# Hydro_Node_Schematic.net
KiCad netlist of a schematic drawn in Altium Designer
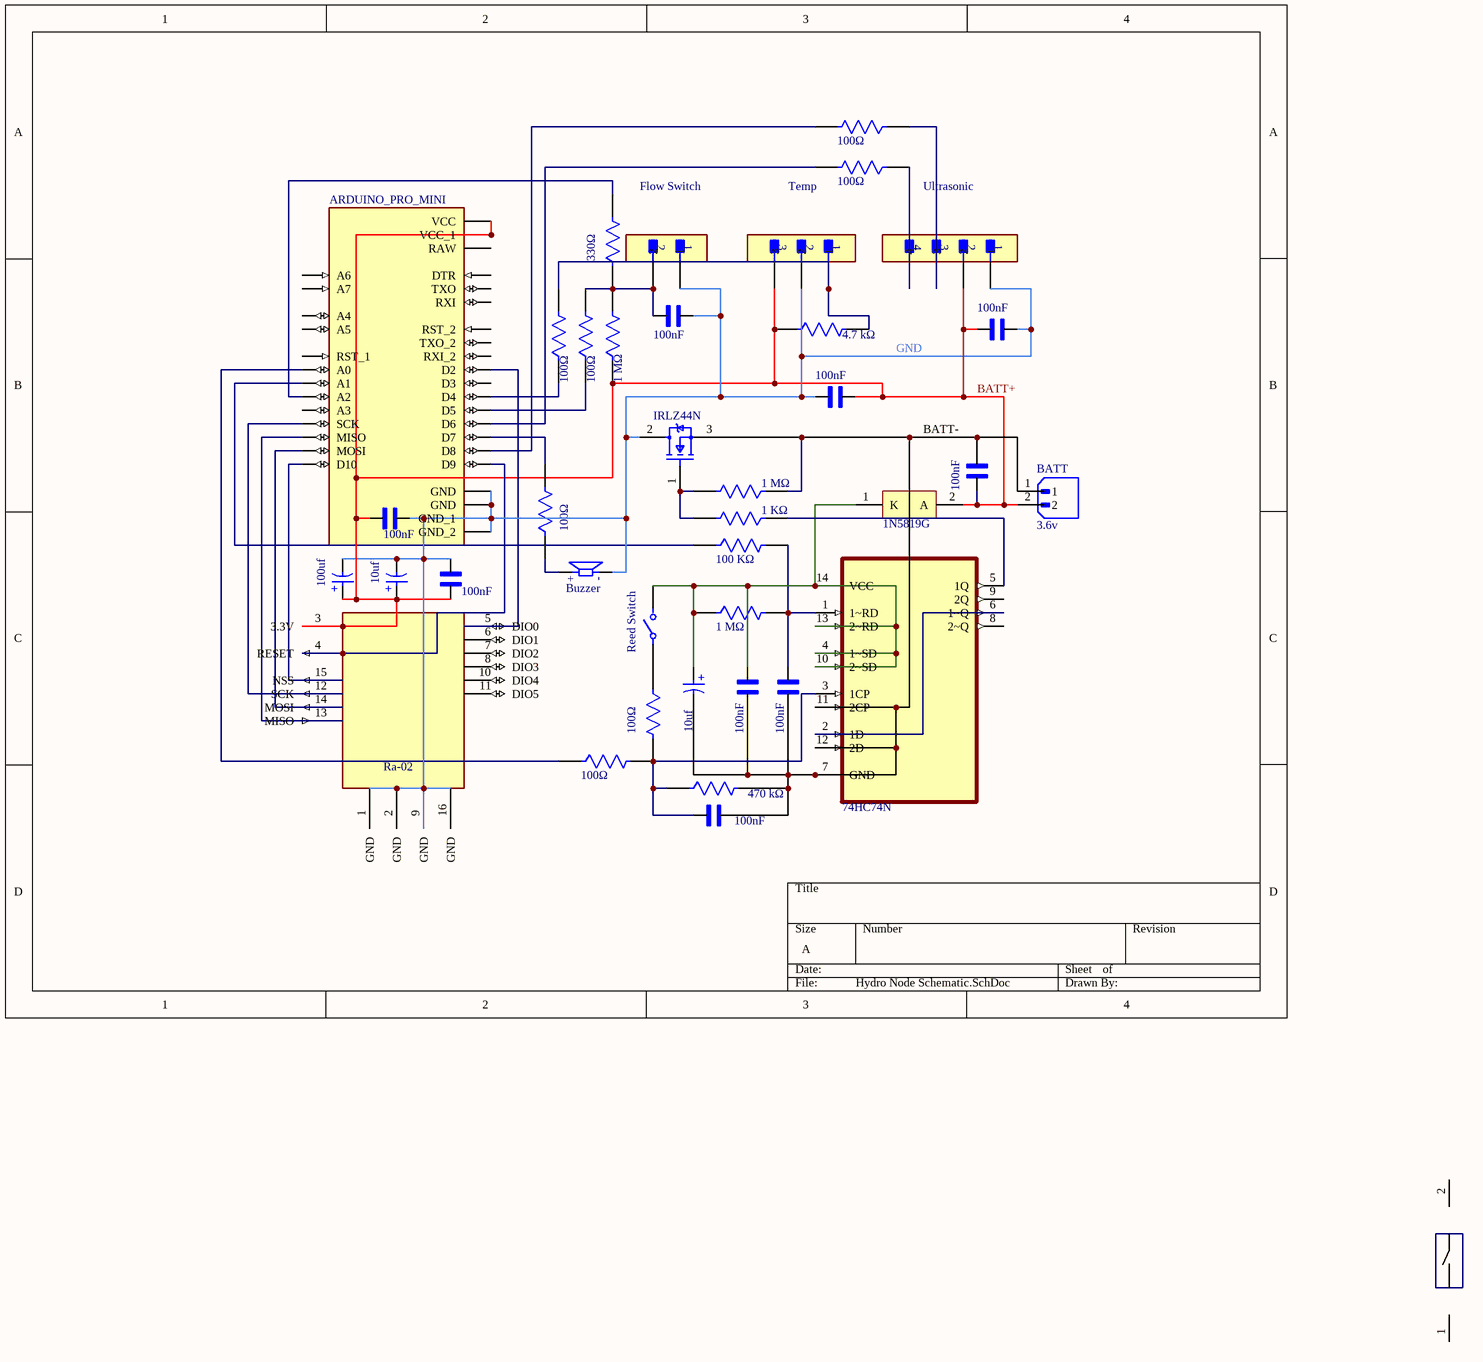
[diagram p0: Hydro Node Schematic.SchDoc]

(export (version "E")
  (design (tool "Eeschema 10.0.6"))
  (components
    (comp (ref "BATT")
      (value "3.6v")
      (footprint "JST_B2B-XH-A_(LF)(SN)")
      (description "Connector Header Through Hole 2 position 0.098 (2.50mm)")
      (fields (field (name "MF") "JST Sales") (field (name "MP") "B2B-XH-A (LF)(SN)"))
      (libsource (lib "B2B-XH-A__LF__SN_") (part "B2B-XH-A_(LF)(SN)"))
    )
    (comp (ref "C1")
      (value "100nF")
      (footprint "CAPRR508W50L508T317H508")
      (description "SR Series 5.08x5.08 mm 100 nF 50 V Â±20% Tol. Z5U Radial Lead/SkyCapÂ®")
      (fields (field (name "MF") "AVX") (field (name "MP") "SR215E104MARTR1"))
      (libsource (lib "SR215E104MARTR1.") (part "SR215E104MARTR1."))
    )
    (comp (ref "C2")
      (value "100nF")
      (footprint "CAPRR508W50L508T317H508")
      (description "SR Series 5.08x5.08 mm 100 nF 50 V Â±20% Tol. Z5U Radial Lead/SkyCapÂ®")
      (fields (field (name "MF") "AVX") (field (name "MP") "SR215E104MARTR1"))
      (libsource (lib "SR215E104MARTR1.") (part "SR215E104MARTR1."))
    )
    (comp (ref "C3")
      (value "100nF")
      (footprint "CAPRR508W50L508T317H508")
      (description "SR Series 5.08x5.08 mm 100 nF 50 V Â±20% Tol. Z5U Radial Lead/SkyCapÂ®")
      (fields (field (name "MF") "AVX") (field (name "MP") "SR215E104MARTR1"))
      (libsource (lib "SR215E104MARTR1.") (part "SR215E104MARTR1."))
    )
    (comp (ref "C4")
      (value "100nF")
      (footprint "CAPRR508W50L508T317H508")
      (description "SR Series 5.08x5.08 mm 100 nF 50 V Â±20% Tol. Z5U Radial Lead/SkyCapÂ®")
      (fields (field (name "MF") "AVX") (field (name "MP") "SR215E104MARTR1"))
      (libsource (lib "") (part "SR215E104MARTR1._1"))
    )
    (comp (ref "C5")
      (value "100nF")
      (footprint "CAPRR508W50L508T317H508")
      (description "SR Series 5.08x5.08 mm 100 nF 50 V Â±20% Tol. Z5U Radial Lead/SkyCapÂ®")
      (fields (field (name "MF") "AVX") (field (name "MP") "SR215E104MARTR1"))
      (libsource (lib "") (part "SR215E104MARTR1._2"))
    )
    (comp (ref "C6")
      (value "100nF")
      (footprint "CAPRR508W50L508T317H508")
      (description "SR Series 5.08x5.08 mm 100 nF 50 V Â±20% Tol. Z5U Radial Lead/SkyCapÂ®")
      (fields (field (name "MF") "AVX") (field (name "MP") "SR215E104MARTR1"))
      (libsource (lib "") (part "SR215E104MARTR1._3"))
    )
    (comp (ref "C7")
      (value "100uf")
      (footprint "WCAP-ATLL_D5H11")
      (description "WCAP-ATLL Aluminum Electrolytic Capacitors")
      (fields (field (name "TOLERANCE") "20%"))
      (libsource (lib "Altium Content Vault") (part "Capacitor_Polarized"))
    )
    (comp (ref "C8")
      (value "10uf")
      (footprint "WCAP-ATLL_D5H11")
      (description "Alum. Electrolytic Cap 10UF 50V 5MM Radial Wcap-atll, Lifetime 4000H +105OC")
      (fields (field (name "TOLERANCE") "20%"))
      (libsource (lib "Altium Content Vault") (part "Capacitor_Polarized"))
    )
    (comp (ref "C9")
      (value "10uf")
      (footprint "WCAP-ATLL_D5H11")
      (description "Alum. Electrolytic Cap 10UF 50V 5MM Radial Wcap-atll, Lifetime 4000H +105OC")
      (fields (field (name "TOLERANCE") "20%"))
      (libsource (lib "Altium Content Vault") (part "Capacitor_Polarized"))
    )
    (comp (ref "C10")
      (value "100nF")
      (footprint "CAPRR508W50L508T317H508")
      (description "SR Series 5.08x5.08 mm 100 nF 50 V Â±20% Tol. Z5U Radial Lead/SkyCapÂ®")
      (fields (field (name "MF") "AVX") (field (name "MP") "SR215E104MARTR1"))
      (libsource (lib "") (part "SR215E104MARTR1._1"))
    )
    (comp (ref "C11")
      (value "100nF")
      (footprint "CAPRR508W50L508T317H508")
      (description "SR Series 5.08x5.08 mm 100 nF 50 V Â±20% Tol. Z5U Radial Lead/SkyCapÂ®")
      (fields (field (name "MF") "AVX") (field (name "MP") "SR215E104MARTR1"))
      (libsource (lib "") (part "SR215E104MARTR1._1"))
    )
    (comp (ref "C12")
      (value "100nF")
      (footprint "CAPRR508W50L508T317H508")
      (description "SR Series 5.08x5.08 mm 100 nF 50 V Â±20% Tol. Z5U Radial Lead/SkyCapÂ®")
      (fields (field (name "MF") "AVX") (field (name "MP") "SR215E104MARTR1"))
      (libsource (lib "SR215E104MARTR1.") (part "SR215E104MARTR1."))
    )
    (comp (ref "D1")
      (value "1N5819G")
      (footprint "ONSC-AXIAL_LEAD-2-59-10_P")
      (description "Rectifier, 2-Pin Axial_Lead, Pb-Free, Bulk Bag")
      (fields (field (name "MANUFACTURER") "On Semiconductor"))
      (libsource (lib "Altium Content Vault") (part "ONSC-D-K1A2-2_A"))
    )
    (comp (ref "J1")
      (value "Flow Switch")
      (footprint "FP-B2B-XH-AM_LF_SN-MFG")
      (description "CONN HEADER VERT 2POS 2.5MM")
      (libsource (lib "Altium Content Vault") (part "3bc925449376181038e59eaffc5286c"))
    )
    (comp (ref "J2")
      (value "Temp")
      (footprint "FP-B3B-XH-A_LF_SN-MFG")
      (description "CONN HEADER VERT 3POS 2.5MM")
      (libsource (lib "Altium Content Vault") (part "0d3f023dd272f625e17a2be33dea85f"))
    )
    (comp (ref "J3")
      (value "Ultrasonic")
      (footprint "FP-B4B-XH-A_LF_SN-MFG")
      (description "CONN HEADER VERT 4POS 2.5MM")
      (libsource (lib "Altium Content Vault") (part "299a8cea1bdcbc3624fe62c390fa72c"))
    )
    (comp (ref "LS1")
      (value "Buzzer")
      (footprint "CUI_CPT-1255C-090:CUI_CPT-1255C-090")
      (description "12 mm, 20 Vp-p, 80 dB, Through Hole, Piezo Audio Transducer Buzzer")
      (fields (field (name "MF") "Same Sky") (field (name "MP") "CPT-1255C-090"))
      (libsource (lib "CPT-1255C-090") (part "CPT-1255C-090"))
    )
    (comp (ref "Q1")
      (value "IRLZ44N")
      (footprint "FP-PG-TO220-3-MFG")
      (description "MOSFET N-CH 55V 47A TO220AB")
      (libsource (lib "Altium Content Vault") (part "b09f7f152735e370c1ea22a33fa83d6"))
    )
    (comp (ref "R1")
      (value "100Ω")
      (footprint "FP-MFR-25-MFG")
      (description "RES 1.18K OHM 1/4W 1% AXIAL")
      (fields (field (name "MANUFACTURER") "Yageo") (field (name "TOLERANCE") "1%"))
      (libsource (lib "Altium Content Vault") (part "1029c3af85768c4190bb7ad29bc67b5"))
    )
    (comp (ref "R2")
      (value "100Ω")
      (footprint "FP-MFR-25-MFG")
      (description "RES 1.18K OHM 1/4W 1% AXIAL")
      (fields (field (name "MANUFACTURER") "Yageo") (field (name "TOLERANCE") "1%"))
      (libsource (lib "Altium Content Vault") (part "1029c3af85768c4190bb7ad29bc67b5"))
    )
    (comp (ref "R3")
      (value "330Ω")
      (footprint "FP-MFR-25-MFG")
      (description "RES 1.18K OHM 1/4W 1% AXIAL")
      (fields (field (name "MANUFACTURER") "Yageo") (field (name "TOLERANCE") "1%"))
      (libsource (lib "Altium Content Vault") (part "1029c3af85768c4190bb7ad29bc67b5"))
    )
    (comp (ref "R4")
      (value "100Ω")
      (footprint "FP-MFR-25-MFG")
      (description "RES 1.18K OHM 1/4W 1% AXIAL")
      (fields (field (name "MANUFACTURER") "Yageo") (field (name "TOLERANCE") "1%"))
      (libsource (lib "Altium Content Vault") (part "1029c3af85768c4190bb7ad29bc67b5"))
    )
    (comp (ref "R5")
      (value "100Ω")
      (footprint "FP-MFR-25-MFG")
      (description "RES 1.18K OHM 1/4W 1% AXIAL")
      (fields (field (name "MANUFACTURER") "Yageo") (field (name "TOLERANCE") "1%"))
      (libsource (lib "Altium Content Vault") (part "1029c3af85768c4190bb7ad29bc67b5"))
    )
    (comp (ref "R6")
      (value "1 MΩ")
      (footprint "FP-MFR-25-MFG")
      (description "RES 1.18K OHM 1/4W 1% AXIAL")
      (fields (field (name "MANUFACTURER") "Yageo") (field (name "TOLERANCE") "1%"))
      (libsource (lib "Altium Content Vault") (part "1029c3af85768c4190bb7ad29bc67b5"))
    )
    (comp (ref "R7")
      (value "4.7 kΩ")
      (footprint "FP-MFR-25-MFG")
      (description "RES 1.18K OHM 1/4W 1% AXIAL")
      (fields (field (name "MANUFACTURER") "Yageo") (field (name "TOLERANCE") "1%"))
      (libsource (lib "Altium Content Vault") (part "1029c3af85768c4190bb7ad29bc67b5"))
    )
    (comp (ref "R8")
      (value "1 MΩ")
      (footprint "FP-MFR-25-MFG")
      (description "RES 1.18K OHM 1/4W 1% AXIAL")
      (fields (field (name "MANUFACTURER") "Yageo") (field (name "TOLERANCE") "1%"))
      (libsource (lib "Altium Content Vault") (part "1029c3af85768c4190bb7ad29bc67b5"))
    )
    (comp (ref "R9")
      (value "100 KΩ")
      (footprint "FP-MFR-25-MFG")
      (description "RES 1.18K OHM 1/4W 1% AXIAL")
      (fields (field (name "MANUFACTURER") "Yageo") (field (name "TOLERANCE") "1%"))
      (libsource (lib "Altium Content Vault") (part "1029c3af85768c4190bb7ad29bc67b5"))
    )
    (comp (ref "R10")
      (value "1 KΩ")
      (footprint "FP-MFR-25-MFG")
      (description "RES 1.18K OHM 1/4W 1% AXIAL")
      (fields (field (name "MANUFACTURER") "Yageo") (field (name "TOLERANCE") "1%"))
      (libsource (lib "Altium Content Vault") (part "1029c3af85768c4190bb7ad29bc67b5"))
    )
    (comp (ref "R11")
      (value "1 MΩ")
      (footprint "FP-MFR-25-MFG")
      (description "RES 1.18K OHM 1/4W 1% AXIAL")
      (fields (field (name "MANUFACTURER") "Yageo") (field (name "TOLERANCE") "1%"))
      (libsource (lib "Altium Content Vault") (part "1029c3af85768c4190bb7ad29bc67b5"))
    )
    (comp (ref "R12")
      (value "100Ω")
      (footprint "FP-MFR-25-MFG")
      (description "RES 1.18K OHM 1/4W 1% AXIAL")
      (fields (field (name "MANUFACTURER") "Yageo") (field (name "TOLERANCE") "1%"))
      (libsource (lib "Altium Content Vault") (part "1029c3af85768c4190bb7ad29bc67b5"))
    )
    (comp (ref "R13")
      (value "100Ω")
      (footprint "FP-MFR-25-MFG")
      (description "RES 1.18K OHM 1/4W 1% AXIAL")
      (fields (field (name "MANUFACTURER") "Yageo") (field (name "TOLERANCE") "1%"))
      (libsource (lib "Altium Content Vault") (part "1029c3af85768c4190bb7ad29bc67b5"))
    )
    (comp (ref "R14")
      (value "470 kΩ")
      (footprint "FP-MFR-25-MFG")
      (description "RES 1.18K OHM 1/4W 1% AXIAL")
      (fields (field (name "MANUFACTURER") "Yageo") (field (name "TOLERANCE") "1%"))
      (libsource (lib "Altium Content Vault") (part "1029c3af85768c4190bb7ad29bc67b5"))
    )
    (comp (ref "R15")
      (value "100Ω")
      (footprint "FP-MFR-25-MFG")
      (description "RES 1.18K OHM 1/4W 1% AXIAL")
      (fields (field (name "MANUFACTURER") "Yageo") (field (name "TOLERANCE") "1%"))
      (libsource (lib "Altium Content Vault") (part "1029c3af85768c4190bb7ad29bc67b5"))
    )
    (comp (ref "S1")
      (value "Reed Switch")
      (footprint "REEDSW-THT-D4L29-P35")
      (fields
        (field (name "MANUFACTURER PART NUMBER") "MDSM-4R-12-18")
        (field (name "OCTOPART") "https://octopart.com/mdsm-4r-12-18-littelfuse-55632078")
        (field (name "MANUFACTURER") "Littelfuse")
      )
      (libsource (lib "ReedSwitch") (part "REED-SWITCH-NO-D4L29"))
    )
    (comp (ref "U1")
      (value "ARDUINO_PRO_MINI")
      (footprint "MODULE_ARDUINO_PRO_MINI")
      (fields (field (name "MF") "Arduino") (field (name "MP") "Arduino Pro Mini"))
      (libsource (lib "ARDUINO_PRO_MINI") (part "ARDUINO_PRO_MINI"))
    )
    (comp (ref "U2")
      (value "74HC74N")
      (footprint "DIP254P762X420-14")
      (description "Flip Flop 2 Element D-Type 1 Bit Positive Edge 14-DIP (0.300, 7.62mm)")
      (fields (field (name "MF") "Nexperia") (field (name "MP") "74HC74N,652"))
      (libsource (lib "74HC74N_652") (part "74HC74N,652"))
    )
    (comp (ref "U3")
      (value "Ra-02")
      (footprint "RA-02_BREAKOUT_THT_2X8")
      (description "Ai-Thinker Ra-02 LoRa transceiver module, SX1278, 410-525 MHz, +18 dBm, SPI, IPEX antenna, SMD-16")
      (fields (field (name "MANUFACTURER") "Ai-Thinker"))
      (libsource (lib "Ra-02") (part "Ra-02"))
    )
  )
  (nets
    (net (code "1") (name "/BATT+") (class "Default")
      (node (ref "BATT") (pin "2") (pinfunction "2_2") (pintype "passive"))
      (node (ref "C2") (pin "1") (pinfunction "1_1") (pintype "passive"))
      (node (ref "C3") (pin "2") (pinfunction "2_2") (pintype "passive"))
      (node (ref "C4") (pin "2") (pinfunction "2_2") (pintype "passive"))
      (node (ref "C5") (pin "2") (pinfunction "2_2") (pintype "passive"))
      (node (ref "C6") (pin "1") (pinfunction "1_1") (pintype "passive"))
      (node (ref "C7") (pin "1") (pinfunction "P_1") (pintype "passive"))
      (node (ref "C8") (pin "1") (pinfunction "P_1") (pintype "passive"))
      (node (ref "D1") (pin "2") (pinfunction "A_2") (pintype "passive"))
      (node (ref "J2") (pin "3") (pinfunction "3_3") (pintype "passive"))
      (node (ref "J3") (pin "2") (pinfunction "2_2") (pintype "passive"))
      (node (ref "R6") (pin "1") (pinfunction "1_1") (pintype "passive"))
      (node (ref "R7") (pin "1") (pinfunction "1_1") (pintype "passive"))
      (node (ref "U1") (pin "JP1_4") (pinfunction "VCC_JP1_4") (pintype "power_in"))
      (node (ref "U1") (pin "JP6_4") (pinfunction "VCC_1_JP6_4") (pintype "power_in"))
      (node (ref "U3") (pin "3") (pinfunction "3.3V_3") (pintype "power_in"))
    )
    (net (code "2") (name "/BATT-") (class "Default")
      (node (ref "BATT") (pin "1") (pinfunction "1_1") (pintype "passive"))
      (node (ref "C10") (pin "2") (pinfunction "2_2") (pintype "passive"))
      (node (ref "C11") (pin "2") (pinfunction "2_2") (pintype "passive"))
      (node (ref "C12") (pin "2") (pinfunction "2_2") (pintype "passive"))
      (node (ref "C4") (pin "1") (pinfunction "1_1") (pintype "passive"))
      (node (ref "C9") (pin "2") (pinfunction "N_2") (pintype "passive"))
      (node (ref "Q1") (pin "3") (pinfunction "S_3") (pintype "passive"))
      (node (ref "R14") (pin "2") (pinfunction "2_2") (pintype "passive"))
      (node (ref "R8") (pin "1") (pinfunction "1_1") (pintype "passive"))
      (node (ref "U2") (pin "11") (pinfunction "2CP_11") (pintype "input"))
      (node (ref "U2") (pin "12") (pinfunction "2D_12") (pintype "input"))
      (node (ref "U2") (pin "7") (pinfunction "GND_7") (pintype "passive"))
    )
    (net (code "3") (name "/GND") (class "Default")
      (node (ref "C1") (pin "2") (pinfunction "2_2") (pintype "passive"))
      (node (ref "C2") (pin "2") (pinfunction "2_2") (pintype "passive"))
      (node (ref "C3") (pin "1") (pinfunction "1_1") (pintype "passive"))
      (node (ref "C5") (pin "1") (pinfunction "1_1") (pintype "passive"))
      (node (ref "C6") (pin "2") (pinfunction "2_2") (pintype "passive"))
      (node (ref "C7") (pin "2") (pinfunction "N_2") (pintype "passive"))
      (node (ref "C8") (pin "2") (pinfunction "N_2") (pintype "passive"))
      (node (ref "J1") (pin "1") (pinfunction "1_1") (pintype "passive"))
      (node (ref "J2") (pin "2") (pinfunction "2_2") (pintype "passive"))
      (node (ref "J3") (pin "1") (pinfunction "1_1") (pintype "passive"))
      (node (ref "LS1") (pin "N") (pinfunction "N_N") (pintype "passive"))
      (node (ref "Q1") (pin "2") (pinfunction "D_2") (pintype "passive"))
      (node (ref "U1") (pin "JP1_5") (pinfunction "GND_JP1_5") (pintype "power_in"))
      (node (ref "U1") (pin "JP1_6") (pinfunction "GND_JP1_6") (pintype "power_in"))
      (node (ref "U1") (pin "JP6_2") (pinfunction "GND_1_JP6_2") (pintype "power_in"))
      (node (ref "U1") (pin "JP7_9") (pinfunction "GND_2_JP7_9") (pintype "power_in"))
      (node (ref "U3") (pin "1") (pinfunction "GND_1") (pintype "power_in"))
      (node (ref "U3") (pin "16") (pinfunction "GND_16") (pintype "power_in"))
      (node (ref "U3") (pin "2") (pinfunction "GND_2") (pintype "power_in"))
      (node (ref "U3") (pin "9") (pinfunction "GND_9") (pintype "power_in"))
    )
    (net (code "4") (name "Net-(C1-Pad1)") (class "Default")
      (node (ref "C1") (pin "1") (pinfunction "1_1") (pintype "passive"))
      (node (ref "J1") (pin "2") (pinfunction "2_2") (pintype "passive"))
      (node (ref "R3") (pin "1") (pinfunction "1_1") (pintype "passive"))
      (node (ref "R5") (pin "2") (pinfunction "2_2") (pintype "passive"))
      (node (ref "R6") (pin "2") (pinfunction "2_2") (pintype "passive"))
    )
    (net (code "5") (name "Net-(C9-P)") (class "Default")
      (node (ref "C10") (pin "1") (pinfunction "1_1") (pintype "passive"))
      (node (ref "C9") (pin "1") (pinfunction "P_1") (pintype "passive"))
      (node (ref "D1") (pin "1") (pinfunction "K_1") (pintype "passive"))
      (node (ref "R11") (pin "1") (pinfunction "1_1") (pintype "passive"))
      (node (ref "S1") (pin "2") (pinfunction "2_2") (pintype "passive"))
      (node (ref "U2") (pin "10") (pinfunction "2~SD_10") (pintype "input"))
      (node (ref "U2") (pin "13") (pinfunction "2~RD_13") (pintype "input"))
      (node (ref "U2") (pin "14") (pinfunction "VCC_14") (pintype "power_in"))
      (node (ref "U2") (pin "4") (pinfunction "1~SD_4") (pintype "input"))
    )
    (net (code "6") (name "Net-(J2-Pad1)") (class "Default")
      (node (ref "J2") (pin "1") (pinfunction "1_1") (pintype "passive"))
      (node (ref "R4") (pin "2") (pinfunction "2_2") (pintype "passive"))
      (node (ref "R7") (pin "2") (pinfunction "2_2") (pintype "passive"))
    )
    (net (code "7") (name "Net-(J3-Pad3)") (class "Default")
      (node (ref "J3") (pin "3") (pinfunction "3_3") (pintype "passive"))
      (node (ref "R1") (pin "1") (pinfunction "1_1") (pintype "passive"))
    )
    (net (code "8") (name "Net-(J3-Pad4)") (class "Default")
      (node (ref "J3") (pin "4") (pinfunction "4_4") (pintype "passive"))
      (node (ref "R2") (pin "1") (pinfunction "1_1") (pintype "passive"))
    )
    (net (code "9") (name "Net-(LS1-PadP)") (class "Default")
      (node (ref "LS1") (pin "P") (pinfunction "P_P") (pintype "passive"))
      (node (ref "R15") (pin "1") (pinfunction "1_1") (pintype "passive"))
    )
    (net (code "10") (name "Net-(Q1-G)") (class "Default")
      (node (ref "Q1") (pin "1") (pinfunction "G_1") (pintype "passive"))
      (node (ref "R10") (pin "2") (pinfunction "2_2") (pintype "passive"))
      (node (ref "R8") (pin "2") (pinfunction "2_2") (pintype "passive"))
    )
    (net (code "11") (name "Net-(R12-Pad1)") (class "Default")
      (node (ref "R12") (pin "1") (pinfunction "1_1") (pintype "passive"))
      (node (ref "S1") (pin "1") (pinfunction "1_1") (pintype "passive"))
    )
    (net (code "12") (name "Net-(U1-A0)") (class "Default")
      (node (ref "R13") (pin "1") (pinfunction "1_1") (pintype "passive"))
      (node (ref "U1") (pin "JP6_8") (pinfunction "A0_JP6_8") (pintype "bidirectional"))
    )
    (net (code "13") (name "Net-(U1-A1)") (class "Default")
      (node (ref "R9") (pin "1") (pinfunction "1_1") (pintype "passive"))
      (node (ref "U1") (pin "JP6_7") (pinfunction "A1_JP6_7") (pintype "bidirectional"))
    )
    (net (code "14") (name "Net-(U1-A2)") (class "Default")
      (node (ref "R3") (pin "2") (pinfunction "2_2") (pintype "passive"))
      (node (ref "U1") (pin "JP6_6") (pinfunction "A2_JP6_6") (pintype "bidirectional"))
    )
    (net (code "15") (name "Net-(U1-D2)") (class "Default")
      (node (ref "U1") (pin "JP7_8") (pinfunction "D2_JP7_8") (pintype "bidirectional"))
      (node (ref "U3") (pin "5") (pinfunction "DIO0_5") (pintype "bidirectional"))
    )
    (net (code "16") (name "Net-(U1-D4)") (class "Default")
      (node (ref "R4") (pin "1") (pinfunction "1_1") (pintype "passive"))
      (node (ref "U1") (pin "JP7_6") (pinfunction "D4_JP7_6") (pintype "bidirectional"))
    )
    (net (code "17") (name "Net-(U1-D5)") (class "Default")
      (node (ref "R5") (pin "1") (pinfunction "1_1") (pintype "passive"))
      (node (ref "U1") (pin "JP7_5") (pinfunction "D5_JP7_5") (pintype "bidirectional"))
    )
    (net (code "18") (name "Net-(U1-D6)") (class "Default")
      (node (ref "R2") (pin "2") (pinfunction "2_2") (pintype "passive"))
      (node (ref "U1") (pin "JP7_4") (pinfunction "D6_JP7_4") (pintype "bidirectional"))
    )
    (net (code "19") (name "Net-(U1-D7)") (class "Default")
      (node (ref "R15") (pin "2") (pinfunction "2_2") (pintype "passive"))
      (node (ref "U1") (pin "JP7_3") (pinfunction "D7_JP7_3") (pintype "bidirectional"))
    )
    (net (code "20") (name "Net-(U1-D8)") (class "Default")
      (node (ref "R1") (pin "2") (pinfunction "2_2") (pintype "passive"))
      (node (ref "U1") (pin "JP7_2") (pinfunction "D8_JP7_2") (pintype "bidirectional"))
    )
    (net (code "21") (name "Net-(U1-D9)") (class "Default")
      (node (ref "U1") (pin "JP7_1") (pinfunction "D9_JP7_1") (pintype "bidirectional"))
      (node (ref "U3") (pin "4") (pinfunction "RESET_4") (pintype "input"))
    )
    (net (code "22") (name "Net-(U1-D10)") (class "Default")
      (node (ref "U1") (pin "JP6_12") (pinfunction "D10_JP6_12") (pintype "bidirectional"))
      (node (ref "U3") (pin "15") (pinfunction "NSS_15") (pintype "input"))
    )
    (net (code "23") (name "Net-(U1-MISO)") (class "Default")
      (node (ref "U1") (pin "JP6_10") (pinfunction "MISO_JP6_10") (pintype "bidirectional"))
      (node (ref "U3") (pin "13") (pinfunction "MISO_13") (pintype "output"))
    )
    (net (code "24") (name "Net-(U1-MOSI)") (class "Default")
      (node (ref "U1") (pin "JP6_11") (pinfunction "MOSI_JP6_11") (pintype "bidirectional"))
      (node (ref "U3") (pin "14") (pinfunction "MOSI_14") (pintype "input"))
    )
    (net (code "25") (name "Net-(U1-SCK)") (class "Default")
      (node (ref "U1") (pin "JP6_9") (pinfunction "SCK_JP6_9") (pintype "bidirectional"))
      (node (ref "U3") (pin "12") (pinfunction "SCK_12") (pintype "input"))
    )
    (net (code "26") (name "Net-(U2-1CP)") (class "Default")
      (node (ref "C12") (pin "1") (pinfunction "1_1") (pintype "passive"))
      (node (ref "R12") (pin "2") (pinfunction "2_2") (pintype "passive"))
      (node (ref "R13") (pin "2") (pinfunction "2_2") (pintype "passive"))
      (node (ref "R14") (pin "1") (pinfunction "1_1") (pintype "passive"))
      (node (ref "U2") (pin "3") (pinfunction "1CP_3") (pintype "input"))
    )
    (net (code "27") (name "Net-(U2-1D)") (class "Default")
      (node (ref "U2") (pin "2") (pinfunction "1D_2") (pintype "input"))
      (node (ref "U2") (pin "6") (pinfunction "1~Q_6") (pintype "output"))
    )
    (net (code "28") (name "Net-(U2-1Q)") (class "Default")
      (node (ref "R10") (pin "1") (pinfunction "1_1") (pintype "passive"))
      (node (ref "U2") (pin "5") (pinfunction "1Q_5") (pintype "output"))
    )
    (net (code "29") (name "Net-(U2-1~RD)") (class "Default")
      (node (ref "C11") (pin "1") (pinfunction "1_1") (pintype "passive"))
      (node (ref "R11") (pin "2") (pinfunction "2_2") (pintype "passive"))
      (node (ref "R9") (pin "2") (pinfunction "2_2") (pintype "passive"))
      (node (ref "U2") (pin "1") (pinfunction "1~RD_1") (pintype "input"))
    )
    (net (code "30") (name "unconnected-(S1-Pad1)") (class "Default")
      (node (ref "S1") (pin "1") (pinfunction "1_1") (pintype "passive"))
    )
    (net (code "31") (name "unconnected-(S1-Pad2)") (class "Default")
      (node (ref "S1") (pin "2") (pinfunction "2_2") (pintype "passive"))
    )
    (net (code "32") (name "unconnected-(U1-A3-PadJP6_5)") (class "Default")
      (node (ref "U1") (pin "JP6_5") (pinfunction "A3_JP6_5") (pintype "bidirectional"))
    )
    (net (code "33") (name "unconnected-(U1-A4-PadJP2_1)") (class "Default")
      (node (ref "U1") (pin "JP2_1") (pinfunction "A4_JP2_1") (pintype "bidirectional"))
    )
    (net (code "34") (name "unconnected-(U1-A5-PadJP2_2)") (class "Default")
      (node (ref "U1") (pin "JP2_2") (pinfunction "A5_JP2_2") (pintype "bidirectional"))
    )
    (net (code "35") (name "unconnected-(U1-A6-PadJP3_1)") (class "Default")
      (node (ref "U1") (pin "JP3_1") (pinfunction "A6_JP3_1") (pintype "input"))
    )
    (net (code "36") (name "unconnected-(U1-A7-PadJP3_2)") (class "Default")
      (node (ref "U1") (pin "JP3_2") (pinfunction "A7_JP3_2") (pintype "input"))
    )
    (net (code "37") (name "unconnected-(U1-D3-PadJP7_7)") (class "Default")
      (node (ref "U1") (pin "JP7_7") (pinfunction "D3_JP7_7") (pintype "bidirectional"))
    )
    (net (code "38") (name "unconnected-(U1-DTR-PadJP1_1)") (class "Default")
      (node (ref "U1") (pin "JP1_1") (pinfunction "DTR_JP1_1") (pintype "input"))
    )
    (net (code "39") (name "unconnected-(U1-RAW-PadJP6_1)") (class "Default")
      (node (ref "U1") (pin "JP6_1") (pinfunction "RAW_JP6_1") (pintype "power_in"))
    )
    (net (code "40") (name "unconnected-(U1-RST_1-PadJP6_3)") (class "Default")
      (node (ref "U1") (pin "JP6_3") (pinfunction "RST_1_JP6_3") (pintype "input"))
    )
    (net (code "41") (name "unconnected-(U1-RST_2-PadJP7_10)") (class "Default")
      (node (ref "U1") (pin "JP7_10") (pinfunction "RST_2_JP7_10") (pintype "input"))
    )
    (net (code "42") (name "unconnected-(U1-RXI-PadJP1_3)") (class "Default")
      (node (ref "U1") (pin "JP1_3") (pinfunction "RXI_JP1_3") (pintype "bidirectional"))
    )
    (net (code "43") (name "unconnected-(U1-RXI_2-PadJP7_11)") (class "Default")
      (node (ref "U1") (pin "JP7_11") (pinfunction "RXI_2_JP7_11") (pintype "bidirectional"))
    )
    (net (code "44") (name "unconnected-(U1-TXO-PadJP1_2)") (class "Default")
      (node (ref "U1") (pin "JP1_2") (pinfunction "TXO_JP1_2") (pintype "bidirectional"))
    )
    (net (code "45") (name "unconnected-(U1-TXO_2-PadJP7_12)") (class "Default")
      (node (ref "U1") (pin "JP7_12") (pinfunction "TXO_2_JP7_12") (pintype "bidirectional"))
    )
    (net (code "46") (name "unconnected-(U2-2Q-Pad9)") (class "Default")
      (node (ref "U2") (pin "9") (pinfunction "2Q_9") (pintype "output"))
    )
    (net (code "47") (name "unconnected-(U2-2~Q-Pad8)") (class "Default")
      (node (ref "U2") (pin "8") (pinfunction "2~Q_8") (pintype "output"))
    )
    (net (code "48") (name "unconnected-(U3-DIO1-Pad6)") (class "Default")
      (node (ref "U3") (pin "6") (pinfunction "DIO1_6") (pintype "bidirectional"))
    )
    (net (code "49") (name "unconnected-(U3-DIO2-Pad7)") (class "Default")
      (node (ref "U3") (pin "7") (pinfunction "DIO2_7") (pintype "bidirectional"))
    )
    (net (code "50") (name "unconnected-(U3-DIO3-Pad8)") (class "Default")
      (node (ref "U3") (pin "8") (pinfunction "DIO3_8") (pintype "bidirectional"))
    )
    (net (code "51") (name "unconnected-(U3-DIO4-Pad10)") (class "Default")
      (node (ref "U3") (pin "10") (pinfunction "DIO4_10") (pintype "bidirectional"))
    )
    (net (code "52") (name "unconnected-(U3-DIO5-Pad11)") (class "Default")
      (node (ref "U3") (pin "11") (pinfunction "DIO5_11") (pintype "bidirectional"))
    )
  )
)
